# light_triggger_attiny44__2.net
KiCad netlist of a schematic drawn in EAGLE
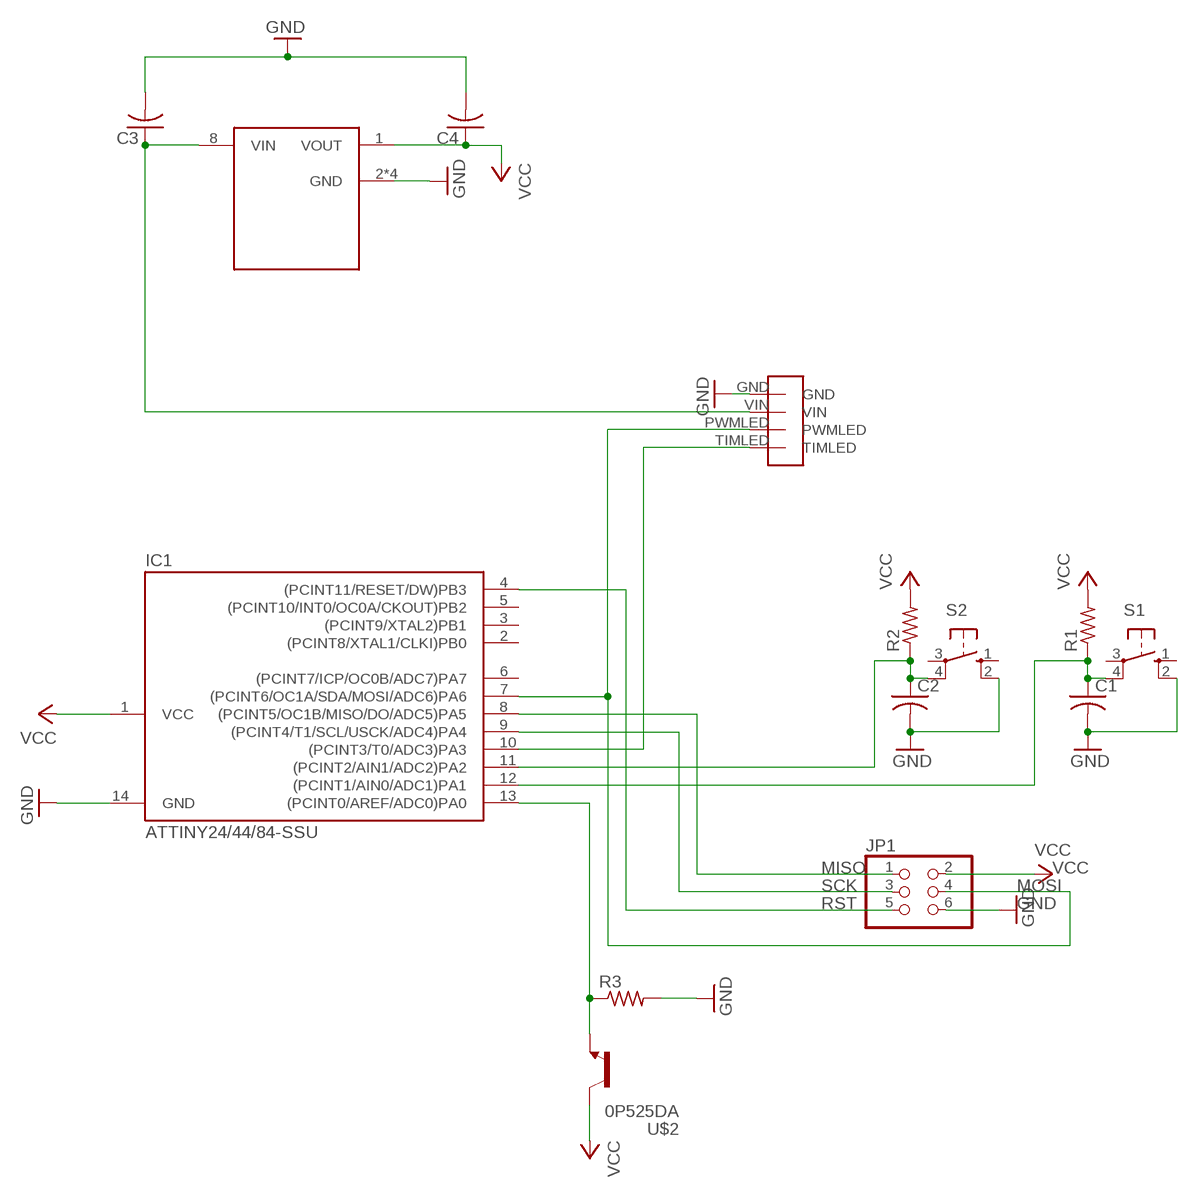
[diagram p0: schematic, sheet 1]

(export (version "E")
  (design (tool "Eeschema 10.0.6"))
  (components
    (comp (ref "C1")
      (value "C-USC0603K")
      (footprint "eagle-import:C0603K")
      (libsource (lib "eagle-import") (part "C-USC0603K"))
    )
    (comp (ref "C2")
      (value "C-USC0603K")
      (footprint "eagle-import:C0603K")
      (libsource (lib "eagle-import") (part "C-USC0603K"))
    )
    (comp (ref "C3")
      (value "C-USC0603K")
      (footprint "eagle-import:C0603K")
      (libsource (lib "eagle-import") (part "C-USC0603K"))
    )
    (comp (ref "C4")
      (value "C-USC0603K")
      (footprint "eagle-import:C0603K")
      (libsource (lib "eagle-import") (part "C-USC0603K"))
    )
    (comp (ref "IC1")
      (value "ATTINY24/44/84-SSU")
      (footprint "eagle-import:SOIC14")
      (libsource (lib "eagle-import") (part "ATTINY24/44/84-SSU"))
    )
    (comp (ref "JP1")
      (value "PINHD-2X3")
      (footprint "eagle-import:2X03")
      (libsource (lib "eagle-import") (part "PINHD-2X3"))
    )
    (comp (ref "R1")
      (value "R-US_R0603")
      (footprint "eagle-import:R0603")
      (libsource (lib "eagle-import") (part "R-US_R0603"))
    )
    (comp (ref "R2")
      (value "R-US_R0603")
      (footprint "eagle-import:R0603")
      (libsource (lib "eagle-import") (part "R-US_R0603"))
    )
    (comp (ref "R3")
      (value "R-US_R0603")
      (footprint "eagle-import:R0603")
      (libsource (lib "eagle-import") (part "R-US_R0603"))
    )
    (comp (ref "S1")
      (value "10-XX")
      (footprint "eagle-import:B3F-10XX")
      (fields (field (name "MPN") "B3F-1000"))
      (libsource (lib "eagle-import") (part "10-XX"))
    )
    (comp (ref "S2")
      (value "10-XX")
      (footprint "eagle-import:B3F-10XX")
      (fields (field (name "MPN") "B3F-1000"))
      (libsource (lib "eagle-import") (part "10-XX"))
    )
    (comp (ref "U$1")
      (value "LM78L05")
      (footprint "eagle-import:LM78L05")
      (libsource (lib "eagle-import") (part "LM78L05"))
    )
    (comp (ref "U$2")
      (value "0P525DA")
      (footprint "eagle-import:PHOTOTRANSITOR(OP525DA)")
      (libsource (lib "eagle-import") (part "0P525DA"))
    )
    (comp (ref "U$3")
      (value "SM04B-GHS-TB")
      (footprint "eagle-import:SM04B-GHS-TB")
      (libsource (lib "eagle-import") (part "SM04B-GHS-TB"))
    )
  )
  (nets
    (net (code "1") (name "/MISO") (class "Default")
      (node (ref "IC1") (pin "8") (pinfunction "(PCINT5/OC1B/MISO/DO/ADC5)PA5_8") (pintype "bidirectional"))
      (node (ref "JP1") (pin "1") (pinfunction "1_1") (pintype "passive"))
    )
    (net (code "2") (name "/MOSI") (class "Default")
      (node (ref "IC1") (pin "7") (pinfunction "(PCINT6/OC1A/SDA/MOSI/ADC6)PA6_7") (pintype "bidirectional"))
      (node (ref "JP1") (pin "4") (pinfunction "4_4") (pintype "passive"))
      (node (ref "U$3") (pin "PWMLED") (pinfunction "PWMLED_PWMLED") (pintype "bidirectional"))
    )
    (net (code "3") (name "/RST") (class "Default")
      (node (ref "IC1") (pin "4") (pinfunction "(PCINT11/RESET/DW)PB3_4") (pintype "bidirectional"))
      (node (ref "JP1") (pin "5") (pinfunction "5_5") (pintype "passive"))
    )
    (net (code "4") (name "/SCK") (class "Default")
      (node (ref "IC1") (pin "9") (pinfunction "(PCINT4/T1/SCL/USCK/ADC4)PA4_9") (pintype "bidirectional"))
      (node (ref "JP1") (pin "3") (pinfunction "3_3") (pintype "passive"))
    )
    (net (code "5") (name "GND") (class "Default")
      (node (ref "C1") (pin "2") (pinfunction "2_2") (pintype "passive"))
      (node (ref "C2") (pin "2") (pinfunction "2_2") (pintype "passive"))
      (node (ref "C3") (pin "2") (pinfunction "2_2") (pintype "passive"))
      (node (ref "C4") (pin "2") (pinfunction "2_2") (pintype "passive"))
      (node (ref "IC1") (pin "14") (pinfunction "GND_14") (pintype "power_in"))
      (node (ref "JP1") (pin "6") (pinfunction "6_6") (pintype "passive"))
      (node (ref "R3") (pin "2") (pinfunction "2_2") (pintype "passive"))
      (node (ref "S1") (pin "2") (pinfunction "S1_2") (pintype "passive"))
      (node (ref "S2") (pin "2") (pinfunction "S1_2") (pintype "passive"))
      (node (ref "U$1") (pin "2") (pinfunction "GND_2") (pintype "bidirectional"))
      (node (ref "U$1") (pin "3") (pinfunction "GND_3") (pintype "bidirectional"))
      (node (ref "U$1") (pin "6") (pinfunction "GND_6") (pintype "bidirectional"))
      (node (ref "U$1") (pin "7") (pinfunction "GND_7") (pintype "bidirectional"))
      (node (ref "U$3") (pin "GND") (pinfunction "GND_GND") (pintype "bidirectional"))
    )
    (net (code "6") (name "Net-(IC1-(PCINT0{slash}AREF{slash}ADC0)PA0)") (class "Default")
      (node (ref "IC1") (pin "13") (pinfunction "(PCINT0/AREF/ADC0)PA0_13") (pintype "bidirectional"))
      (node (ref "R3") (pin "1") (pinfunction "1_1") (pintype "passive"))
      (node (ref "U$2") (pin "P$2") (pinfunction "E_P$2") (pintype "passive"))
    )
    (net (code "7") (name "Net-(IC1-(PCINT1{slash}AIN0{slash}ADC1)PA1)") (class "Default")
      (node (ref "C1") (pin "1") (pinfunction "1_1") (pintype "passive"))
      (node (ref "IC1") (pin "12") (pinfunction "(PCINT1/AIN0/ADC1)PA1_12") (pintype "bidirectional"))
      (node (ref "R1") (pin "1") (pinfunction "1_1") (pintype "passive"))
      (node (ref "S1") (pin "4") (pinfunction "P1_4") (pintype "passive"))
    )
    (net (code "8") (name "Net-(IC1-(PCINT2{slash}AIN1{slash}ADC2)PA2)") (class "Default")
      (node (ref "C2") (pin "1") (pinfunction "1_1") (pintype "passive"))
      (node (ref "IC1") (pin "11") (pinfunction "(PCINT2/AIN1/ADC2)PA2_11") (pintype "bidirectional"))
      (node (ref "R2") (pin "1") (pinfunction "1_1") (pintype "passive"))
      (node (ref "S2") (pin "4") (pinfunction "P1_4") (pintype "passive"))
    )
    (net (code "9") (name "Net-(IC1-(PCINT3{slash}T0{slash}ADC3)PA3)") (class "Default")
      (node (ref "IC1") (pin "10") (pinfunction "(PCINT3/T0/ADC3)PA3_10") (pintype "bidirectional"))
      (node (ref "U$3") (pin "TIMLED") (pinfunction "TIMLED_TIMLED") (pintype "bidirectional"))
    )
    (net (code "10") (name "Net-(U$1-VIN)") (class "Default")
      (node (ref "C3") (pin "1") (pinfunction "1_1") (pintype "passive"))
      (node (ref "U$1") (pin "8") (pinfunction "VIN_8") (pintype "bidirectional"))
      (node (ref "U$3") (pin "VIN") (pinfunction "VIN_VIN") (pintype "bidirectional"))
    )
    (net (code "11") (name "VCC") (class "Default")
      (node (ref "C4") (pin "1") (pinfunction "1_1") (pintype "passive"))
      (node (ref "IC1") (pin "1") (pinfunction "VCC_1") (pintype "power_in"))
      (node (ref "JP1") (pin "2") (pinfunction "2_2") (pintype "passive"))
      (node (ref "R1") (pin "2") (pinfunction "2_2") (pintype "passive"))
      (node (ref "R2") (pin "2") (pinfunction "2_2") (pintype "passive"))
      (node (ref "U$1") (pin "1") (pinfunction "VOUT_1") (pintype "bidirectional"))
      (node (ref "U$2") (pin "P$1") (pinfunction "C_P$1") (pintype "passive"))
    )
    (net (code "12") (name "unconnected-(IC1-(PCINT7{slash}ICP{slash}OC0B{slash}ADC7)PA7-Pad6)") (class "Default")
      (node (ref "IC1") (pin "6") (pinfunction "(PCINT7/ICP/OC0B/ADC7)PA7_6") (pintype "bidirectional"))
    )
    (net (code "13") (name "unconnected-(IC1-(PCINT8{slash}XTAL1{slash}CLKI)PB0-Pad2)") (class "Default")
      (node (ref "IC1") (pin "2") (pinfunction "(PCINT8/XTAL1/CLKI)PB0_2") (pintype "bidirectional"))
    )
    (net (code "14") (name "unconnected-(IC1-(PCINT9{slash}XTAL2)PB1-Pad3)") (class "Default")
      (node (ref "IC1") (pin "3") (pinfunction "(PCINT9/XTAL2)PB1_3") (pintype "bidirectional"))
    )
    (net (code "15") (name "unconnected-(IC1-(PCINT10{slash}INT0{slash}OC0A{slash}CKOUT)PB2-Pad5)") (class "Default")
      (node (ref "IC1") (pin "5") (pinfunction "(PCINT10/INT0/OC0A/CKOUT)PB2_5") (pintype "bidirectional"))
    )
    (net (code "16") (name "unconnected-(S1-P-Pad3)") (class "Default")
      (node (ref "S1") (pin "3") (pinfunction "P_3") (pintype "passive"))
    )
    (net (code "17") (name "unconnected-(S1-S-Pad1)") (class "Default")
      (node (ref "S1") (pin "1") (pinfunction "S_1") (pintype "passive"))
    )
    (net (code "18") (name "unconnected-(S2-P-Pad3)") (class "Default")
      (node (ref "S2") (pin "3") (pinfunction "P_3") (pintype "passive"))
    )
    (net (code "19") (name "unconnected-(S2-S-Pad1)") (class "Default")
      (node (ref "S2") (pin "1") (pinfunction "S_1") (pintype "passive"))
    )
  )
)
